# LowerMachine.net
KiCad netlist of a schematic drawn in Altium Designer
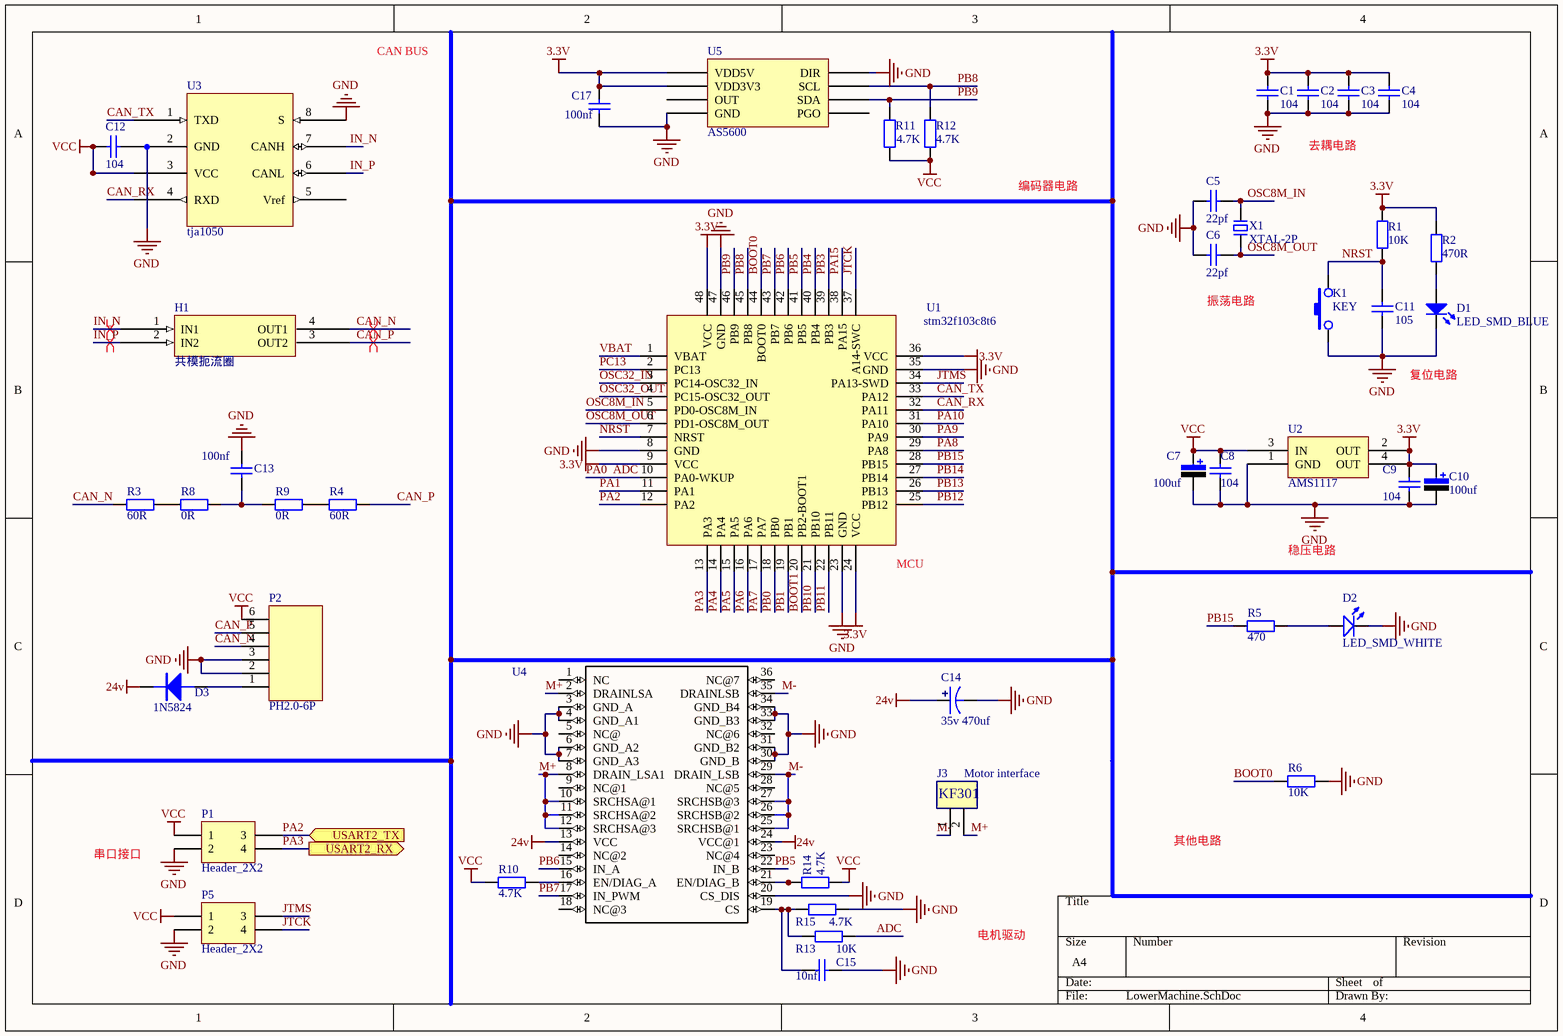
[diagram p0: LowerMachine.SchDoc]

(export (version "E")
  (design (tool "Eeschema 10.0.6"))
  (components
    (comp (ref "C1") (value "104") (footprint "Cap-0603") (libsource (lib "最小系统元件库") (part "CAP")))
    (comp (ref "C2") (value "104") (footprint "Cap-0603") (libsource (lib "最小系统元件库") (part "CAP")))
    (comp (ref "C3") (value "104") (footprint "Cap-0603") (libsource (lib "最小系统元件库") (part "CAP")))
    (comp (ref "C4") (value "104") (footprint "Cap-0603") (libsource (lib "最小系统元件库") (part "CAP")))
    (comp (ref "C5") (value "22pf") (footprint "Cap-0603") (libsource (lib "最小系统元件库") (part "CAP")))
    (comp (ref "C6") (value "22pf") (footprint "Cap-0603") (libsource (lib "最小系统元件库") (part "CAP")))
    (comp (ref "C7") (value "100uf") (footprint "tan_cap_C") (libsource (lib "最小系统元件库") (part "tan_cap")))
    (comp (ref "C8") (value "104") (footprint "Cap-0603-M") (libsource (lib "最小系统元件库") (part "CAP")))
    (comp (ref "C9") (value "104") (footprint "Cap-0603-M") (libsource (lib "最小系统元件库") (part "CAP")))
    (comp (ref "C10") (value "100uf") (footprint "tan_cap_C") (libsource (lib "最小系统元件库") (part "tan_cap")))
    (comp (ref "C11") (value "105") (footprint "Cap-0603") (libsource (lib "最小系统元件库") (part "CAP")))
    (comp (ref "C12") (value "104") (footprint "Cap-0603") (libsource (lib "最小系统元件库") (part "CAP")))
    (comp (ref "C13") (value "100nf") (footprint "Cap-0603") (libsource (lib "最小系统元件库") (part "CAP")))
    (comp (ref "C14")
      (value "35v 470uf")
      (footprint "CAPE_G_10X10.3X10.2")
      (description "贴片电解电容")
      (libsource (lib "Miscellaneous Base") (part "CAPE-SMD"))
    )
    (comp (ref "C15")
      (value "10nf")
      (footprint "Cap-0603")
      (description "贴片陶瓷电容")
      (libsource (lib "Miscellaneous Base") (part "CAP"))
    )
    (comp (ref "C17")
      (value "100nf")
      (footprint "Cap-0603")
      (description "贴片陶瓷电容")
      (libsource (lib "Miscellaneous Base") (part "CAP"))
    )
    (comp (ref "D1")
      (value "LED_SMD_BLUE")
      (footprint "LED_0603_B")
      (description "发光二极管")
      (libsource (lib "Miscellaneous Transistor") (part "LED_SMD_BLUE"))
    )
    (comp (ref "D2")
      (value "LED_SMD_WHITE")
      (footprint "LED_0603_W")
      (description "发光二极管")
      (libsource (lib "Miscellaneous Transistor") (part "LED_SMD_WHITE"))
    )
    (comp (ref "D3")
      (value "1N5824")
      (footprint "DO-214AC/SMA")
      (description "普通二极管")
      (libsource (lib "Miscellaneous Transistor") (part "DIODE"))
    )
    (comp (ref "H1") (value "共模扼流圈") (footprint "共模扼流圈") (libsource (lib "CAN步进控制板元件库") (part "共模扼流圈")))
    (comp (ref "J3")
      (value "Motor interface")
      (footprint "KF301-5.0-2P")
      (libsource (lib "KF301") (part "KF301-2P"))
    )
    (comp (ref "K1")
      (value "KEY")
      (footprint "SW-SMD-2X4")
      (libsource (lib "Miscellaneous Switch") (part "KEY"))
    )
    (comp (ref "P1")
      (value "Header_2X2")
      (footprint "Header_SMD_2.54X2")
      (libsource (lib "Miscellaneous Header") (part "Header_2X2"))
    )
    (comp (ref "P2") (value "PH2.0-6P") (footprint "PH2.0S-6P") (libsource (lib "PH") (part "PH2.0-6P")))
    (comp (ref "P5")
      (value "Header_2X2")
      (footprint "Header_SMD_2.54X2")
      (libsource (lib "Miscellaneous Header") (part "Header_2X2"))
    )
    (comp (ref "R1")
      (value "10K")
      (footprint "Res-0603")
      (description "贴片电阻")
      (libsource (lib "") (part "RES_3"))
    )
    (comp (ref "R2")
      (value "470R")
      (footprint "Res-0603")
      (description "贴片电阻")
      (libsource (lib "") (part "RES_3"))
    )
    (comp (ref "R3")
      (value "60R")
      (footprint "Res-0603")
      (description "贴片电阻")
      (libsource (lib "Miscellaneous Base") (part "RES"))
    )
    (comp (ref "R4")
      (value "60R")
      (footprint "Res-0603")
      (description "贴片电阻")
      (libsource (lib "Miscellaneous Base") (part "RES"))
    )
    (comp (ref "R5")
      (value "470")
      (footprint "Res-0603")
      (description "贴片电阻")
      (libsource (lib "Miscellaneous Base") (part "RES"))
    )
    (comp (ref "R6")
      (value "10K")
      (footprint "Res-0603")
      (description "贴片电阻")
      (libsource (lib "") (part "RES_1"))
    )
    (comp (ref "R8")
      (value "0R")
      (footprint "Res-0603")
      (description "贴片电阻")
      (libsource (lib "Miscellaneous Base") (part "RES"))
    )
    (comp (ref "R9")
      (value "0R")
      (footprint "Res-0603")
      (description "贴片电阻")
      (libsource (lib "Miscellaneous Base") (part "RES"))
    )
    (comp (ref "R10")
      (value "4.7K")
      (footprint "Res-0603")
      (description "贴片电阻")
      (libsource (lib "") (part "RES_1"))
    )
    (comp (ref "R11")
      (value "4.7K")
      (footprint "Res-0603")
      (description "贴片电阻")
      (libsource (lib "") (part "RES_2"))
    )
    (comp (ref "R12")
      (value "4.7K")
      (footprint "Res-0603")
      (description "贴片电阻")
      (libsource (lib "") (part "RES_2"))
    )
    (comp (ref "R13")
      (value "10K")
      (footprint "Res-0603")
      (description "贴片电阻")
      (libsource (lib "") (part "RES_1"))
    )
    (comp (ref "R14")
      (value "4.7K")
      (footprint "Res-0603")
      (description "贴片电阻")
      (libsource (lib "") (part "RES_1"))
    )
    (comp (ref "R15")
      (value "4.7K")
      (footprint "Res-0603")
      (description "贴片电阻")
      (libsource (lib "") (part "RES_1"))
    )
    (comp (ref "U1")
      (value "stm32f103c8t6")
      (footprint "stm32f103c8t6")
      (libsource (lib "最小系统元件库") (part "stm32f103c8t6"))
    )
    (comp (ref "U2") (value "AMS1117") (footprint "AMS1117") (libsource (lib "最小系统元件库") (part "AMS1117")))
    (comp (ref "U3") (value "tja1050") (footprint "tja1050") (libsource (lib "CAN步进控制板元件库") (part "tja1050")))
    (comp (ref "U4")
      (value "VNH5180A-E")
      (footprint "*SSO-36")
      (description "Automotive fully integrated H-bridge motor driver")
      (fields (field (name "MF") "STMicroelectronics"))
      (libsource (lib "VNH5180A-E") (part "VNH5180A-E"))
    )
    (comp (ref "U5")
      (value "AS5600")
      (footprint "AS5600")
      (libsource (lib "LowerMachineSchlib") (part "AS5600"))
    )
    (comp (ref "X1")
      (value "XTAL-2P")
      (footprint "OSC 5032-2P")
      (description "2脚无源脚晶振")
      (libsource (lib "Miscellaneous XTAL") (part "XTAL-2P"))
    )
  )
  (nets
    (net (code "1") (name "/ADC") (class "Default")
      (node (ref "R13") (pin "1") (pinfunction "1_1") (pintype "passive"))
      (node (ref "U1") (pin "10") (pinfunction "PA0-WKUP_10") (pintype "passive"))
    )
    (net (code "2") (name "/BOOT0") (class "Default")
      (node (ref "R6") (pin "2") (pinfunction "2_2") (pintype "passive"))
      (node (ref "U1") (pin "44") (pinfunction "BOOT0_44") (pintype "passive"))
    )
    (net (code "3") (name "/BOOT1") (class "Default")
      (node (ref "U1") (pin "20") (pinfunction "PB2-BOOT1_20") (pintype "passive"))
    )
    (net (code "4") (name "/CAN_N") (class "Default")
      (node (ref "H1") (pin "4") (pinfunction "OUT1_4") (pintype "passive"))
      (node (ref "P2") (pin "4") (pinfunction "4_4") (pintype "passive"))
      (node (ref "R3") (pin "1") (pinfunction "1_1") (pintype "passive"))
    )
    (net (code "5") (name "/CAN_P") (class "Default")
      (node (ref "H1") (pin "3") (pinfunction "OUT2_3") (pintype "passive"))
      (node (ref "P2") (pin "5") (pinfunction "5_5") (pintype "passive"))
      (node (ref "R4") (pin "2") (pinfunction "2_2") (pintype "passive"))
    )
    (net (code "6") (name "/CAN_RX") (class "Default")
      (node (ref "U1") (pin "32") (pinfunction "PA11_32") (pintype "passive"))
      (node (ref "U3") (pin "4") (pinfunction "RXD_4") (pintype "output"))
    )
    (net (code "7") (name "/CAN_TX") (class "Default")
      (node (ref "U1") (pin "33") (pinfunction "PA12_33") (pintype "passive"))
      (node (ref "U3") (pin "1") (pinfunction "TXD_1") (pintype "input"))
    )
    (net (code "8") (name "/IN_N") (class "Default")
      (node (ref "H1") (pin "1") (pinfunction "IN1_1") (pintype "input"))
      (node (ref "U3") (pin "7") (pinfunction "CANH_7") (pintype "bidirectional"))
    )
    (net (code "9") (name "/IN_P") (class "Default")
      (node (ref "H1") (pin "2") (pinfunction "IN2_2") (pintype "input"))
      (node (ref "U3") (pin "6") (pinfunction "CANL_6") (pintype "bidirectional"))
    )
    (net (code "10") (name "/JTCK") (class "Default")
      (node (ref "P5") (pin "4") (pinfunction "4_4") (pintype "passive"))
      (node (ref "U1") (pin "37") (pinfunction "A14-SWC_37") (pintype "passive"))
    )
    (net (code "11") (name "/JTMS") (class "Default")
      (node (ref "P5") (pin "3") (pinfunction "3_3") (pintype "passive"))
      (node (ref "U1") (pin "34") (pinfunction "PA13-SWD_34") (pintype "passive"))
    )
    (net (code "12") (name "/M+") (class "Default")
      (node (ref "J3") (pin "2") (pinfunction "2_2") (pintype "passive"))
      (node (ref "U4") (pin "10") (pinfunction "SRCHSA@1_10") (pintype "bidirectional"))
      (node (ref "U4") (pin "11") (pinfunction "SRCHSA@2_11") (pintype "bidirectional"))
      (node (ref "U4") (pin "12") (pinfunction "SRCHSA@3_12") (pintype "bidirectional"))
      (node (ref "U4") (pin "2") (pinfunction "DRAINLSA_2") (pintype "bidirectional"))
      (node (ref "U4") (pin "8") (pinfunction "DRAIN_LSA1_8") (pintype "bidirectional"))
    )
    (net (code "13") (name "/M-") (class "Default")
      (node (ref "J3") (pin "1") (pinfunction "1_1") (pintype "passive"))
      (node (ref "U4") (pin "25") (pinfunction "SRCHSB@1_25") (pintype "bidirectional"))
      (node (ref "U4") (pin "26") (pinfunction "SRCHSB@2_26") (pintype "bidirectional"))
      (node (ref "U4") (pin "27") (pinfunction "SRCHSB@3_27") (pintype "bidirectional"))
      (node (ref "U4") (pin "29") (pinfunction "DRAIN_LSB_29") (pintype "bidirectional"))
      (node (ref "U4") (pin "35") (pinfunction "DRAINLSB_35") (pintype "bidirectional"))
    )
    (net (code "14") (name "/NRST") (class "Default")
      (node (ref "C11") (pin "2") (pinfunction "2_2") (pintype "passive"))
      (node (ref "K1") (pin "3") (pinfunction "3_3") (pintype "passive"))
      (node (ref "R1") (pin "2") (pinfunction "2_2") (pintype "passive"))
      (node (ref "U1") (pin "7") (pinfunction "NRST_7") (pintype "passive"))
    )
    (net (code "15") (name "/OSC8M_IN") (class "Default")
      (node (ref "C5") (pin "1") (pinfunction "1_1") (pintype "passive"))
      (node (ref "U1") (pin "5") (pinfunction "PD0-OSC8M_IN_5") (pintype "passive"))
      (node (ref "X1") (pin "2") (pinfunction "2_2") (pintype "passive"))
    )
    (net (code "16") (name "/OSC8M_OUT") (class "Default")
      (node (ref "C6") (pin "1") (pinfunction "1_1") (pintype "passive"))
      (node (ref "U1") (pin "6") (pinfunction "PD1-OSC8M_OUT_6") (pintype "passive"))
      (node (ref "X1") (pin "1") (pinfunction "1_1") (pintype "passive"))
    )
    (net (code "17") (name "/OSC32_IN") (class "Default")
      (node (ref "U1") (pin "3") (pinfunction "PC14-OSC32_IN_3") (pintype "passive"))
    )
    (net (code "18") (name "/OSC32_OUT") (class "Default")
      (node (ref "U1") (pin "4") (pinfunction "PC15-OSC32_OUT_4") (pintype "passive"))
    )
    (net (code "19") (name "/PA1") (class "Default")
      (node (ref "U1") (pin "11") (pinfunction "PA1_11") (pintype "passive"))
    )
    (net (code "20") (name "/PA2") (class "Default")
      (node (ref "P1") (pin "3") (pinfunction "3_3") (pintype "passive"))
      (node (ref "U1") (pin "12") (pinfunction "PA2_12") (pintype "passive"))
    )
    (net (code "21") (name "/PA3") (class "Default")
      (node (ref "P1") (pin "4") (pinfunction "4_4") (pintype "passive"))
      (node (ref "U1") (pin "13") (pinfunction "PA3_13") (pintype "passive"))
    )
    (net (code "22") (name "/PA4") (class "Default")
      (node (ref "U1") (pin "14") (pinfunction "PA4_14") (pintype "passive"))
    )
    (net (code "23") (name "/PA5") (class "Default")
      (node (ref "U1") (pin "15") (pinfunction "PA5_15") (pintype "passive"))
    )
    (net (code "24") (name "/PA6") (class "Default")
      (node (ref "U1") (pin "16") (pinfunction "PA6_16") (pintype "passive"))
    )
    (net (code "25") (name "/PA7") (class "Default")
      (node (ref "U1") (pin "17") (pinfunction "PA7_17") (pintype "passive"))
    )
    (net (code "26") (name "/PA8") (class "Default")
      (node (ref "U1") (pin "29") (pinfunction "PA8_29") (pintype "passive"))
    )
    (net (code "27") (name "/PA9") (class "Default")
      (node (ref "U1") (pin "30") (pinfunction "PA9_30") (pintype "passive"))
    )
    (net (code "28") (name "/PA10") (class "Default")
      (node (ref "U1") (pin "31") (pinfunction "PA10_31") (pintype "passive"))
    )
    (net (code "29") (name "/PA15") (class "Default")
      (node (ref "U1") (pin "38") (pinfunction "PA15_38") (pintype "passive"))
    )
    (net (code "30") (name "/PB0") (class "Default")
      (node (ref "U1") (pin "18") (pinfunction "PB0_18") (pintype "passive"))
    )
    (net (code "31") (name "/PB1") (class "Default")
      (node (ref "U1") (pin "19") (pinfunction "PB1_19") (pintype "passive"))
    )
    (net (code "32") (name "/PB3") (class "Default")
      (node (ref "U1") (pin "39") (pinfunction "PB3_39") (pintype "passive"))
    )
    (net (code "33") (name "/PB4") (class "Default")
      (node (ref "U1") (pin "40") (pinfunction "PB4_40") (pintype "passive"))
    )
    (net (code "34") (name "/PB5") (class "Default")
      (node (ref "U1") (pin "41") (pinfunction "PB5_41") (pintype "passive"))
      (node (ref "U4") (pin "22") (pinfunction "IN_B_22") (pintype "bidirectional"))
    )
    (net (code "35") (name "/PB6") (class "Default")
      (node (ref "U1") (pin "42") (pinfunction "PB6_42") (pintype "passive"))
      (node (ref "U4") (pin "15") (pinfunction "IN_A_15") (pintype "bidirectional"))
    )
    (net (code "36") (name "/PB7") (class "Default")
      (node (ref "U1") (pin "43") (pinfunction "PB7_43") (pintype "passive"))
      (node (ref "U4") (pin "17") (pinfunction "IN_PWM_17") (pintype "bidirectional"))
    )
    (net (code "37") (name "/PB8") (class "Default")
      (node (ref "R12") (pin "2") (pinfunction "2_2") (pintype "passive"))
      (node (ref "U1") (pin "45") (pinfunction "PB8_45") (pintype "passive"))
      (node (ref "U5") (pin "7") (pinfunction "SCL_7") (pintype "passive"))
    )
    (net (code "38") (name "/PB9") (class "Default")
      (node (ref "R11") (pin "2") (pinfunction "2_2") (pintype "passive"))
      (node (ref "U1") (pin "46") (pinfunction "PB9_46") (pintype "passive"))
      (node (ref "U5") (pin "6") (pinfunction "SDA_6") (pintype "passive"))
    )
    (net (code "39") (name "/PB10") (class "Default")
      (node (ref "U1") (pin "21") (pinfunction "PB10_21") (pintype "passive"))
    )
    (net (code "40") (name "/PB11") (class "Default")
      (node (ref "U1") (pin "22") (pinfunction "PB11_22") (pintype "passive"))
    )
    (net (code "41") (name "/PB12") (class "Default")
      (node (ref "U1") (pin "25") (pinfunction "PB12_25") (pintype "passive"))
    )
    (net (code "42") (name "/PB13") (class "Default")
      (node (ref "U1") (pin "26") (pinfunction "PB13_26") (pintype "passive"))
    )
    (net (code "43") (name "/PB14") (class "Default")
      (node (ref "U1") (pin "27") (pinfunction "PB14_27") (pintype "passive"))
    )
    (net (code "44") (name "/PB15") (class "Default")
      (node (ref "R5") (pin "1") (pinfunction "1_1") (pintype "passive"))
      (node (ref "U1") (pin "28") (pinfunction "PB15_28") (pintype "passive"))
    )
    (net (code "45") (name "/PC13") (class "Default")
      (node (ref "U1") (pin "2") (pinfunction "PC13_2") (pintype "passive"))
    )
    (net (code "46") (name "/VBAT") (class "Default")
      (node (ref "U1") (pin "1") (pinfunction "VBAT_1") (pintype "passive"))
    )
    (net (code "47") (name "3.3V") (class "Default")
      (node (ref "C1") (pin "2") (pinfunction "2_2") (pintype "passive"))
      (node (ref "C10") (pin "1") (pinfunction "1_1") (pintype "passive"))
      (node (ref "C17") (pin "2") (pinfunction "2_2") (pintype "passive"))
      (node (ref "C2") (pin "2") (pinfunction "2_2") (pintype "passive"))
      (node (ref "C3") (pin "2") (pinfunction "2_2") (pintype "passive"))
      (node (ref "C4") (pin "2") (pinfunction "2_2") (pintype "passive"))
      (node (ref "C9") (pin "2") (pinfunction "2_2") (pintype "passive"))
      (node (ref "R1") (pin "1") (pinfunction "1_1") (pintype "passive"))
      (node (ref "R2") (pin "1") (pinfunction "1_1") (pintype "passive"))
      (node (ref "U1") (pin "24") (pinfunction "VCC_24") (pintype "passive"))
      (node (ref "U1") (pin "36") (pinfunction "VCC_36") (pintype "passive"))
      (node (ref "U1") (pin "48") (pinfunction "VCC_48") (pintype "passive"))
      (node (ref "U1") (pin "9") (pinfunction "VCC_9") (pintype "passive"))
      (node (ref "U2") (pin "2") (pinfunction "OUT_2") (pintype "passive"))
      (node (ref "U2") (pin "4") (pinfunction "OUT_4") (pintype "passive"))
      (node (ref "U5") (pin "1") (pinfunction "VDD5V_1") (pintype "passive"))
      (node (ref "U5") (pin "2") (pinfunction "VDD3V3_2") (pintype "passive"))
    )
    (net (code "48") (name "24v") (class "Default")
      (node (ref "C14") (pin "1") (pinfunction "1_1") (pintype "passive"))
      (node (ref "D3") (pin "K") (pinfunction "K_K") (pintype "passive"))
      (node (ref "U4") (pin "13") (pinfunction "VCC_13") (pintype "bidirectional"))
      (node (ref "U4") (pin "24") (pinfunction "VCC@1_24") (pintype "bidirectional"))
    )
    (net (code "49") (name "GND") (class "Default")
      (node (ref "C1") (pin "1") (pinfunction "1_1") (pintype "passive"))
      (node (ref "C10") (pin "2") (pinfunction "2_2") (pintype "passive"))
      (node (ref "C11") (pin "1") (pinfunction "1_1") (pintype "passive"))
      (node (ref "C13") (pin "2") (pinfunction "2_2") (pintype "passive"))
      (node (ref "C14") (pin "2") (pinfunction "2_2") (pintype "passive"))
      (node (ref "C15") (pin "2") (pinfunction "2_2") (pintype "passive"))
      (node (ref "C17") (pin "1") (pinfunction "1_1") (pintype "passive"))
      (node (ref "C2") (pin "1") (pinfunction "1_1") (pintype "passive"))
      (node (ref "C3") (pin "1") (pinfunction "1_1") (pintype "passive"))
      (node (ref "C4") (pin "1") (pinfunction "1_1") (pintype "passive"))
      (node (ref "C5") (pin "2") (pinfunction "2_2") (pintype "passive"))
      (node (ref "C6") (pin "2") (pinfunction "2_2") (pintype "passive"))
      (node (ref "C7") (pin "2") (pinfunction "2_2") (pintype "passive"))
      (node (ref "C8") (pin "1") (pinfunction "1_1") (pintype "passive"))
      (node (ref "C9") (pin "1") (pinfunction "1_1") (pintype "passive"))
      (node (ref "D1") (pin "1") (pinfunction "K_1") (pintype "passive"))
      (node (ref "D2") (pin "2") (pinfunction "K_2") (pintype "passive"))
      (node (ref "K1") (pin "1") (pinfunction "1_1") (pintype "passive"))
      (node (ref "P1") (pin "2") (pinfunction "2_2") (pintype "passive"))
      (node (ref "P2") (pin "2") (pinfunction "2_2") (pintype "passive"))
      (node (ref "P2") (pin "3") (pinfunction "3_3") (pintype "passive"))
      (node (ref "P5") (pin "2") (pinfunction "2_2") (pintype "passive"))
      (node (ref "R15") (pin "1") (pinfunction "1_1") (pintype "passive"))
      (node (ref "R6") (pin "1") (pinfunction "1_1") (pintype "passive"))
      (node (ref "U1") (pin "23") (pinfunction "GND_23") (pintype "passive"))
      (node (ref "U1") (pin "35") (pinfunction "GND_35") (pintype "passive"))
      (node (ref "U1") (pin "47") (pinfunction "GND_47") (pintype "passive"))
      (node (ref "U1") (pin "8") (pinfunction "GND_8") (pintype "passive"))
      (node (ref "U2") (pin "1") (pinfunction "GND_1") (pintype "passive"))
      (node (ref "U3") (pin "8") (pinfunction "S_8") (pintype "input"))
      (node (ref "U4") (pin "20") (pinfunction "CS_DIS_20") (pintype "bidirectional"))
      (node (ref "U4") (pin "3") (pinfunction "GND_A_3") (pintype "bidirectional"))
      (node (ref "U4") (pin "30") (pinfunction "GND_B_30") (pintype "bidirectional"))
      (node (ref "U4") (pin "31") (pinfunction "GND_B2_31") (pintype "bidirectional"))
      (node (ref "U4") (pin "33") (pinfunction "GND_B3_33") (pintype "bidirectional"))
      (node (ref "U4") (pin "34") (pinfunction "GND_B4_34") (pintype "bidirectional"))
      (node (ref "U4") (pin "4") (pinfunction "GND_A1_4") (pintype "bidirectional"))
      (node (ref "U4") (pin "6") (pinfunction "GND_A2_6") (pintype "bidirectional"))
      (node (ref "U4") (pin "7") (pinfunction "GND_A3_7") (pintype "bidirectional"))
      (node (ref "U5") (pin "4") (pinfunction "GND_4") (pintype "passive"))
      (node (ref "U5") (pin "8") (pinfunction "DIR_8") (pintype "passive"))
    )
    (net (code "50") (name "Net-(C13-Pad1)") (class "Default")
      (node (ref "C13") (pin "1") (pinfunction "1_1") (pintype "passive"))
      (node (ref "R8") (pin "2") (pinfunction "2_2") (pintype "passive"))
      (node (ref "R9") (pin "1") (pinfunction "1_1") (pintype "passive"))
    )
    (net (code "51") (name "Net-(D1-A)") (class "Default")
      (node (ref "D1") (pin "2") (pinfunction "A_2") (pintype "passive"))
      (node (ref "R2") (pin "2") (pinfunction "2_2") (pintype "passive"))
    )
    (net (code "52") (name "Net-(D2-A)") (class "Default")
      (node (ref "D2") (pin "1") (pinfunction "A_1") (pintype "passive"))
      (node (ref "R5") (pin "2") (pinfunction "2_2") (pintype "passive"))
    )
    (net (code "53") (name "Net-(D3-PadA)") (class "Default")
      (node (ref "D3") (pin "A") (pinfunction "A_A") (pintype "passive"))
      (node (ref "P2") (pin "1") (pinfunction "1_1") (pintype "passive"))
    )
    (net (code "54") (name "Net-(R3-Pad2)") (class "Default")
      (node (ref "R3") (pin "2") (pinfunction "2_2") (pintype "passive"))
      (node (ref "R8") (pin "1") (pinfunction "1_1") (pintype "passive"))
    )
    (net (code "55") (name "Net-(R4-Pad1)") (class "Default")
      (node (ref "R4") (pin "1") (pinfunction "1_1") (pintype "passive"))
      (node (ref "R9") (pin "2") (pinfunction "2_2") (pintype "passive"))
    )
    (net (code "56") (name "Net-(U3-GND)") (class "Default")
      (node (ref "C12") (pin "2") (pinfunction "2_2") (pintype "passive"))
      (node (ref "U3") (pin "2") (pinfunction "GND_2") (pintype "power_in"))
    )
    (net (code "57") (name "Net-(U4-CS)") (class "Default")
      (node (ref "C15") (pin "1") (pinfunction "1_1") (pintype "passive"))
      (node (ref "R13") (pin "2") (pinfunction "2_2") (pintype "passive"))
      (node (ref "R15") (pin "2") (pinfunction "2_2") (pintype "passive"))
      (node (ref "U4") (pin "19") (pinfunction "CS_19") (pintype "bidirectional"))
    )
    (net (code "58") (name "Net-(U4-EN{slash}DIAG_A)") (class "Default")
      (node (ref "R10") (pin "1") (pinfunction "1_1") (pintype "passive"))
      (node (ref "U4") (pin "16") (pinfunction "EN/DIAG_A_16") (pintype "bidirectional"))
    )
    (net (code "59") (name "Net-(U4-EN{slash}DIAG_B)") (class "Default")
      (node (ref "R14") (pin "2") (pinfunction "2_2") (pintype "passive"))
      (node (ref "U4") (pin "21") (pinfunction "EN/DIAG_B_21") (pintype "bidirectional"))
    )
    (net (code "60") (name "VCC") (class "Default")
      (node (ref "C12") (pin "1") (pinfunction "1_1") (pintype "passive"))
      (node (ref "C7") (pin "1") (pinfunction "1_1") (pintype "passive"))
      (node (ref "C8") (pin "2") (pinfunction "2_2") (pintype "passive"))
      (node (ref "P1") (pin "1") (pinfunction "1_1") (pintype "passive"))
      (node (ref "P2") (pin "6") (pinfunction "6_6") (pintype "passive"))
      (node (ref "P5") (pin "1") (pinfunction "1_1") (pintype "passive"))
      (node (ref "R10") (pin "2") (pinfunction "2_2") (pintype "passive"))
      (node (ref "R11") (pin "1") (pinfunction "1_1") (pintype "passive"))
      (node (ref "R12") (pin "1") (pinfunction "1_1") (pintype "passive"))
      (node (ref "R14") (pin "1") (pinfunction "1_1") (pintype "passive"))
      (node (ref "U2") (pin "3") (pinfunction "IN_3") (pintype "passive"))
      (node (ref "U3") (pin "3") (pinfunction "VCC_3") (pintype "power_in"))
    )
    (net (code "61") (name "unconnected-(U3-Vref-Pad5)") (class "Default")
      (node (ref "U3") (pin "5") (pinfunction "Vref_5") (pintype "output"))
    )
    (net (code "62") (name "unconnected-(U4-NC-Pad1)") (class "Default")
      (node (ref "U4") (pin "1") (pinfunction "NC_1") (pintype "bidirectional"))
    )
    (net (code "63") (name "unconnected-(U4-NC@-Pad5)") (class "Default")
      (node (ref "U4") (pin "5") (pinfunction "NC@_5") (pintype "bidirectional"))
    )
    (net (code "64") (name "unconnected-(U4-NC@1-Pad9)") (class "Default")
      (node (ref "U4") (pin "9") (pinfunction "NC@1_9") (pintype "bidirectional"))
    )
    (net (code "65") (name "unconnected-(U4-NC@2-Pad14)") (class "Default")
      (node (ref "U4") (pin "14") (pinfunction "NC@2_14") (pintype "bidirectional"))
    )
    (net (code "66") (name "unconnected-(U4-NC@3-Pad18)") (class "Default")
      (node (ref "U4") (pin "18") (pinfunction "NC@3_18") (pintype "bidirectional"))
    )
    (net (code "67") (name "unconnected-(U4-NC@4-Pad23)") (class "Default")
      (node (ref "U4") (pin "23") (pinfunction "NC@4_23") (pintype "bidirectional"))
    )
    (net (code "68") (name "unconnected-(U4-NC@5-Pad28)") (class "Default")
      (node (ref "U4") (pin "28") (pinfunction "NC@5_28") (pintype "bidirectional"))
    )
    (net (code "69") (name "unconnected-(U4-NC@6-Pad32)") (class "Default")
      (node (ref "U4") (pin "32") (pinfunction "NC@6_32") (pintype "bidirectional"))
    )
    (net (code "70") (name "unconnected-(U4-NC@7-Pad36)") (class "Default")
      (node (ref "U4") (pin "36") (pinfunction "NC@7_36") (pintype "bidirectional"))
    )
    (net (code "71") (name "unconnected-(U5-OUT-Pad3)") (class "Default")
      (node (ref "U5") (pin "3") (pinfunction "OUT_3") (pintype "passive"))
    )
    (net (code "72") (name "unconnected-(U5-PGO-Pad5)") (class "Default")
      (node (ref "U5") (pin "5") (pinfunction "PGO_5") (pintype "passive"))
    )
  )
)
